# usb_speaker.net
KiCad netlist of a schematic drawn in EAGLE
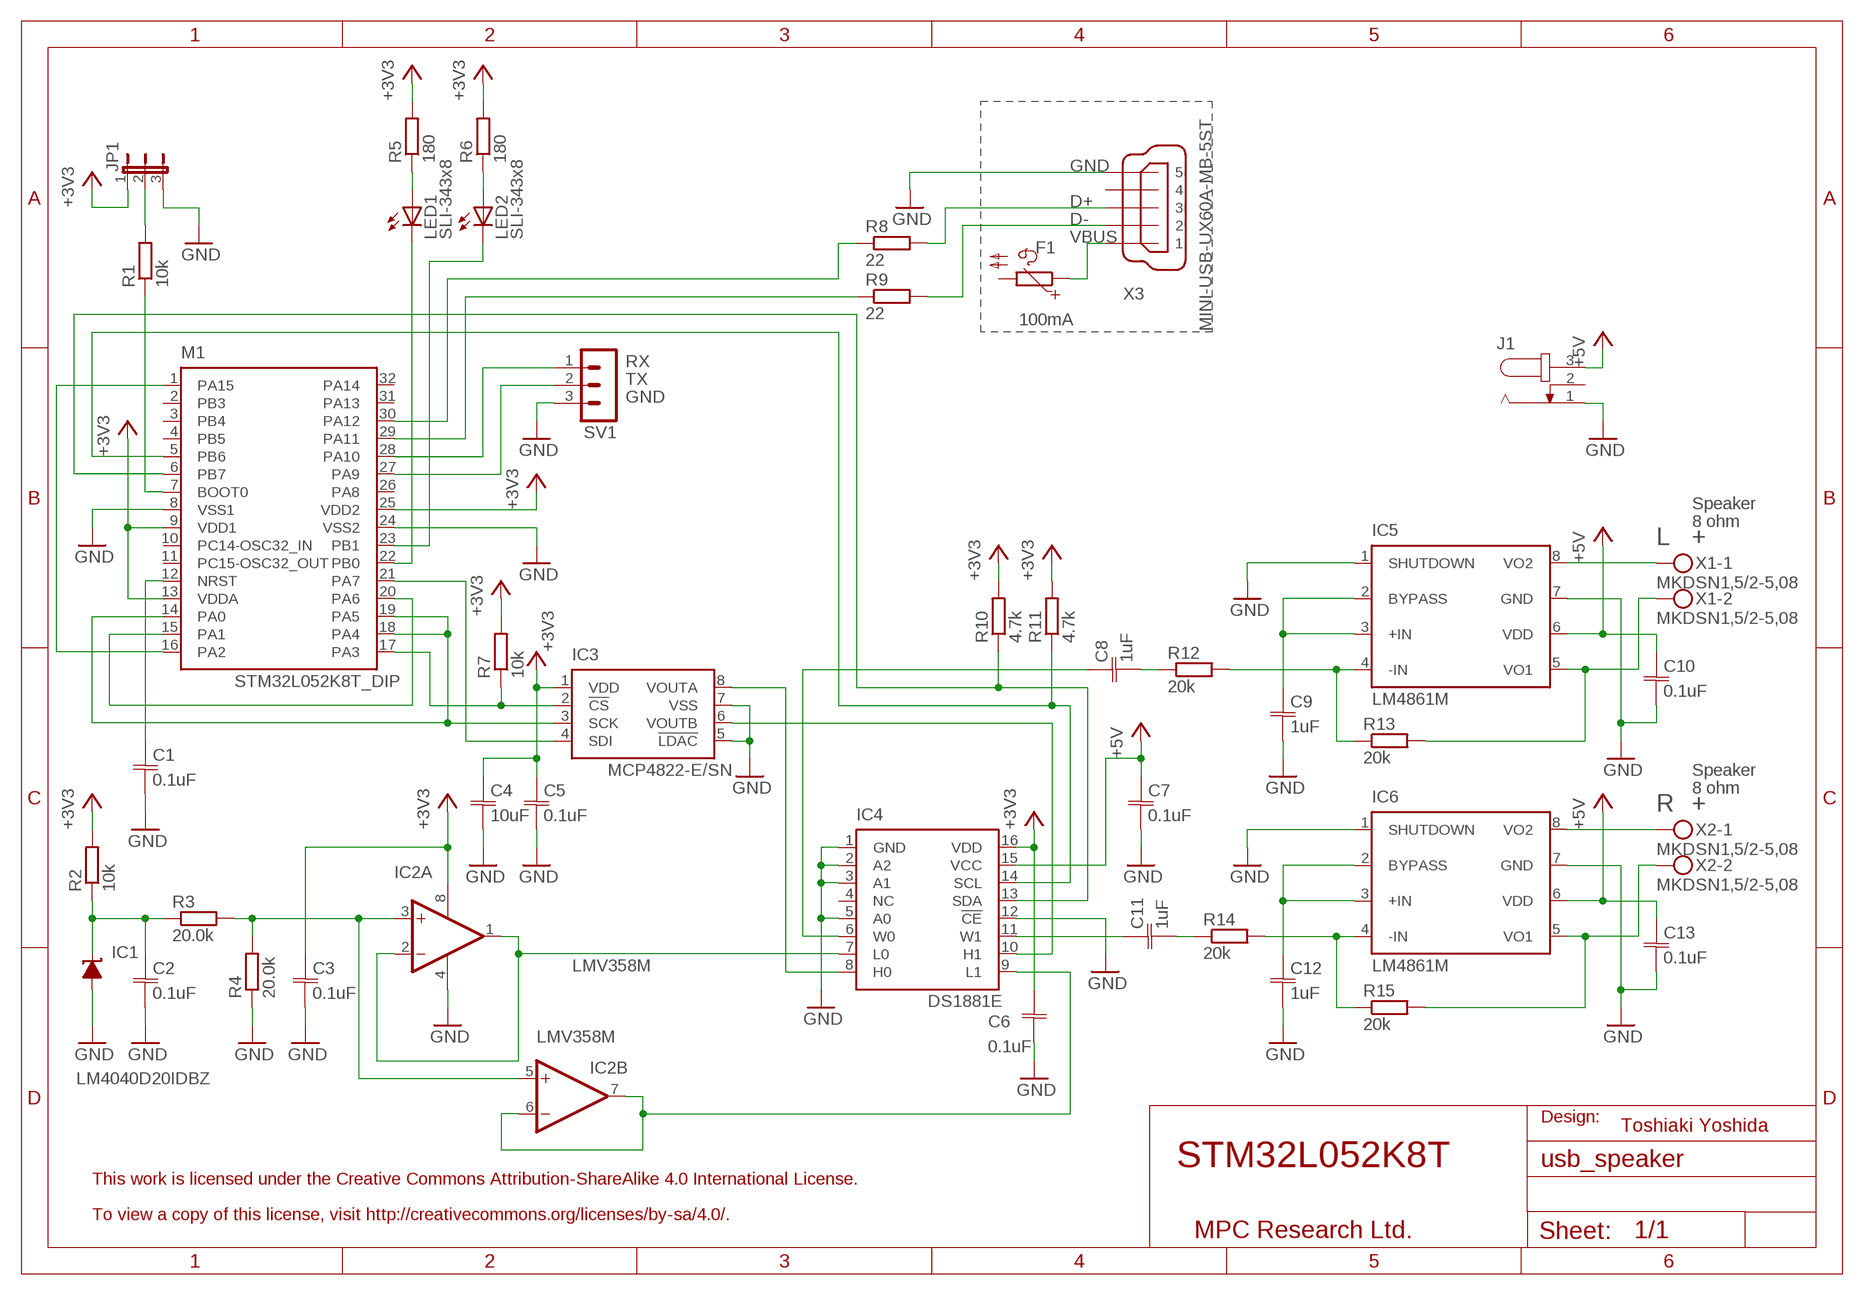
[diagram p0: schematic, sheet 1]

(export (version "E")
  (design (tool "Eeschema 10.0.6"))
  (components
    (comp (ref "C1")
      (value "0.1uF")
      (footprint "eagle-import:C050-024X044")
      (libsource (lib "eagle-import") (part "C-JIS050-024X044"))
    )
    (comp (ref "C2")
      (value "0.1uF")
      (footprint "eagle-import:C050-024X044")
      (libsource (lib "eagle-import") (part "C-JIS050-024X044"))
    )
    (comp (ref "C3")
      (value "0.1uF")
      (footprint "eagle-import:C050-024X044")
      (libsource (lib "eagle-import") (part "C-JIS050-024X044"))
    )
    (comp (ref "C4")
      (value "10uF")
      (footprint "eagle-import:C050-024X044")
      (libsource (lib "eagle-import") (part "C-JIS050-024X044"))
    )
    (comp (ref "C5")
      (value "0.1uF")
      (footprint "eagle-import:C050-024X044")
      (libsource (lib "eagle-import") (part "C-JIS050-024X044"))
    )
    (comp (ref "C6")
      (value "0.1uF")
      (footprint "eagle-import:C050-024X044")
      (libsource (lib "eagle-import") (part "C-JIS050-024X044"))
    )
    (comp (ref "C7")
      (value "0.1uF")
      (footprint "eagle-import:C050-024X044")
      (libsource (lib "eagle-import") (part "C-JIS050-024X044"))
    )
    (comp (ref "C8")
      (value "1uF")
      (footprint "eagle-import:C050-024X044")
      (libsource (lib "eagle-import") (part "C-JIS050-024X044"))
    )
    (comp (ref "C9")
      (value "1uF")
      (footprint "eagle-import:C050-024X044")
      (libsource (lib "eagle-import") (part "C-JIS050-024X044"))
    )
    (comp (ref "C10")
      (value "0.1uF")
      (footprint "eagle-import:C050-024X044")
      (libsource (lib "eagle-import") (part "C-JIS050-024X044"))
    )
    (comp (ref "C11")
      (value "1uF")
      (footprint "eagle-import:C050-024X044")
      (libsource (lib "eagle-import") (part "C-JIS050-024X044"))
    )
    (comp (ref "C12")
      (value "1uF")
      (footprint "eagle-import:C050-024X044")
      (libsource (lib "eagle-import") (part "C-JIS050-024X044"))
    )
    (comp (ref "C13")
      (value "0.1uF")
      (footprint "eagle-import:C050-024X044")
      (libsource (lib "eagle-import") (part "C-JIS050-024X044"))
    )
    (comp (ref "F1")
      (value "100mA")
      (footprint "eagle-import:1206")
      (libsource (lib "eagle-import") (part "PTC1206"))
    )
    (comp (ref "IC1")
      (value "LM4040D20IDBZ")
      (footprint "eagle-import:DBZ_R-PDSO-G3")
      (fields (field (name "MPN") "LM4041A12IDBZR"))
      (libsource (lib "eagle-import") (part "LM4041DBZA12"))
    )
    (comp (ref "IC2")
      (value "LMV358M")
      (footprint "eagle-import:SO08")
      (libsource (lib "eagle-import") (part "LMV358?M"))
    )
    (comp (ref "IC3")
      (value "MCP4822-E/SN")
      (footprint "eagle-import:SO-08")
      (libsource (lib "eagle-import") (part "MCP482-E/SN2"))
    )
    (comp (ref "IC4")
      (value "DS1881E")
      (footprint "eagle-import:TSSP16")
      (libsource (lib "eagle-import") (part "DS1881E"))
    )
    (comp (ref "IC5")
      (value "LM4861M")
      (footprint "eagle-import:SO-08")
      (libsource (lib "eagle-import") (part "LM4861M"))
    )
    (comp (ref "IC6")
      (value "LM4861M")
      (footprint "eagle-import:SO-08")
      (libsource (lib "eagle-import") (part "LM4861M"))
    )
    (comp (ref "J1")
      (value "JACK-PLUG0")
      (footprint "eagle-import:SPC4077")
      (libsource (lib "eagle-import") (part "JACK-PLUG0"))
    )
    (comp (ref "JP1")
      (value "JP2E")
      (footprint "eagle-import:JP2")
      (libsource (lib "eagle-import") (part "JP2E"))
    )
    (comp (ref "LED1")
      (value "SLI-343x8")
      (footprint "eagle-import:LED3MM")
      (libsource (lib "eagle-import") (part "LED3MM"))
    )
    (comp (ref "LED2")
      (value "SLI-343x8")
      (footprint "eagle-import:LED3MM")
      (libsource (lib "eagle-import") (part "LED3MM"))
    )
    (comp (ref "M1")
      (value "STM32L052K8T_DIP")
      (footprint "eagle-import:DIP32")
      (libsource (lib "eagle-import") (part "STM32L052K8T_DIP"))
    )
    (comp (ref "R1")
      (value "10k")
      (footprint "eagle-import:0207_2V")
      (libsource (lib "eagle-import") (part "R-EU_0207/2V"))
    )
    (comp (ref "R2")
      (value "10k")
      (footprint "eagle-import:0207_2V")
      (libsource (lib "eagle-import") (part "R-EU_0207/2V"))
    )
    (comp (ref "R3")
      (value "20.0k")
      (footprint "eagle-import:0207_2V")
      (libsource (lib "eagle-import") (part "R-EU_0207/2V"))
    )
    (comp (ref "R4")
      (value "20.0k")
      (footprint "eagle-import:0207_2V")
      (libsource (lib "eagle-import") (part "R-EU_0207/2V"))
    )
    (comp (ref "R5")
      (value "180")
      (footprint "eagle-import:0207_2V")
      (libsource (lib "eagle-import") (part "R-EU_0207/2V"))
    )
    (comp (ref "R6")
      (value "180")
      (footprint "eagle-import:0207_2V")
      (libsource (lib "eagle-import") (part "R-EU_0207/2V"))
    )
    (comp (ref "R7")
      (value "10k")
      (footprint "eagle-import:0207_2V")
      (libsource (lib "eagle-import") (part "R-EU_0207/2V"))
    )
    (comp (ref "R8")
      (value "22")
      (footprint "eagle-import:0207_10")
      (libsource (lib "eagle-import") (part "R-EU_0207/10"))
    )
    (comp (ref "R9")
      (value "22")
      (footprint "eagle-import:0207_10")
      (libsource (lib "eagle-import") (part "R-EU_0207/10"))
    )
    (comp (ref "R10")
      (value "4.7k")
      (footprint "eagle-import:0207_2V")
      (libsource (lib "eagle-import") (part "R-EU_0207/2V"))
    )
    (comp (ref "R11")
      (value "4.7k")
      (footprint "eagle-import:0207_2V")
      (libsource (lib "eagle-import") (part "R-EU_0207/2V"))
    )
    (comp (ref "R12")
      (value "20k")
      (footprint "eagle-import:0207_2V")
      (libsource (lib "eagle-import") (part "R-EU_0207/2V"))
    )
    (comp (ref "R13")
      (value "20k")
      (footprint "eagle-import:0207_10")
      (libsource (lib "eagle-import") (part "R-EU_0207/10"))
    )
    (comp (ref "R14")
      (value "20k")
      (footprint "eagle-import:0207_2V")
      (libsource (lib "eagle-import") (part "R-EU_0207/2V"))
    )
    (comp (ref "R15")
      (value "20k")
      (footprint "eagle-import:0207_10")
      (libsource (lib "eagle-import") (part "R-EU_0207/10"))
    )
    (comp (ref "SV1")
      (value "MA03-1")
      (footprint "eagle-import:MA03-1")
      (libsource (lib "eagle-import") (part "MA03-1"))
    )
    (comp (ref "X1")
      (value "MKDSN1,5/2-5,08")
      (footprint "eagle-import:MKDSN1,5_2-5,08")
      (libsource (lib "eagle-import") (part "MKDSN1,5/2-5,08"))
    )
    (comp (ref "X2")
      (value "MKDSN1,5/2-5,08")
      (footprint "eagle-import:MKDSN1,5_2-5,08")
      (libsource (lib "eagle-import") (part "MKDSN1,5/2-5,08"))
    )
    (comp (ref "X3")
      (value "MINI-USB-UX60A-MB-5ST")
      (footprint "eagle-import:UX60A-MB-5ST")
      (libsource (lib "eagle-import") (part "MINI-USB-UX60A-MB-5ST"))
    )
  )
  (nets
    (net (code "1") (name "+3V3") (class "Default")
      (node (ref "C3") (pin "1") (pinfunction "1_1") (pintype "passive"))
      (node (ref "C4") (pin "1") (pinfunction "1_1") (pintype "passive"))
      (node (ref "C5") (pin "1") (pinfunction "1_1") (pintype "passive"))
      (node (ref "C6") (pin "1") (pinfunction "1_1") (pintype "passive"))
      (node (ref "IC2") (pin "8") (pinfunction "V+_8") (pintype "power_in"))
      (node (ref "IC3") (pin "1") (pinfunction "VDD_1") (pintype "power_in"))
      (node (ref "IC4") (pin "16") (pinfunction "VDD_16") (pintype "power_in"))
      (node (ref "JP1") (pin "1") (pinfunction "1_1") (pintype "passive"))
      (node (ref "M1") (pin "13") (pinfunction "VDDA_13") (pintype "power_in"))
      (node (ref "M1") (pin "25") (pinfunction "VDD2_25") (pintype "bidirectional"))
      (node (ref "M1") (pin "9") (pinfunction "VDD1_9") (pintype "power_in"))
      (node (ref "R10") (pin "2") (pinfunction "2_2") (pintype "passive"))
      (node (ref "R11") (pin "2") (pinfunction "2_2") (pintype "passive"))
      (node (ref "R2") (pin "2") (pinfunction "2_2") (pintype "passive"))
      (node (ref "R5") (pin "2") (pinfunction "2_2") (pintype "passive"))
      (node (ref "R6") (pin "2") (pinfunction "2_2") (pintype "passive"))
      (node (ref "R7") (pin "2") (pinfunction "2_2") (pintype "passive"))
    )
    (net (code "2") (name "+5V") (class "Default")
      (node (ref "C10") (pin "1") (pinfunction "1_1") (pintype "passive"))
      (node (ref "C13") (pin "1") (pinfunction "1_1") (pintype "passive"))
      (node (ref "C7") (pin "1") (pinfunction "1_1") (pintype "passive"))
      (node (ref "IC4") (pin "15") (pinfunction "VCC_15") (pintype "power_in"))
      (node (ref "IC5") (pin "6") (pinfunction "VDD_6") (pintype "power_in"))
      (node (ref "IC6") (pin "6") (pinfunction "VDD_6") (pintype "power_in"))
      (node (ref "J1") (pin "3") (pinfunction "3_3") (pintype "passive"))
    )
    (net (code "3") (name "GND") (class "Default")
      (node (ref "C1") (pin "2") (pinfunction "2_2") (pintype "passive"))
      (node (ref "C10") (pin "2") (pinfunction "2_2") (pintype "passive"))
      (node (ref "C12") (pin "2") (pinfunction "2_2") (pintype "passive"))
      (node (ref "C13") (pin "2") (pinfunction "2_2") (pintype "passive"))
      (node (ref "C2") (pin "2") (pinfunction "2_2") (pintype "passive"))
      (node (ref "C3") (pin "2") (pinfunction "2_2") (pintype "passive"))
      (node (ref "C4") (pin "2") (pinfunction "2_2") (pintype "passive"))
      (node (ref "C5") (pin "2") (pinfunction "2_2") (pintype "passive"))
      (node (ref "C6") (pin "2") (pinfunction "2_2") (pintype "passive"))
      (node (ref "C7") (pin "2") (pinfunction "2_2") (pintype "passive"))
      (node (ref "C9") (pin "2") (pinfunction "2_2") (pintype "passive"))
      (node (ref "IC1") (pin "2") (pinfunction "A_2") (pintype "passive"))
      (node (ref "IC2") (pin "4") (pinfunction "V-_4") (pintype "power_in"))
      (node (ref "IC3") (pin "5") (pinfunction "~{LDAC}_5") (pintype "input"))
      (node (ref "IC3") (pin "7") (pinfunction "VSS_7") (pintype "power_in"))
      (node (ref "IC4") (pin "1") (pinfunction "GND_1") (pintype "power_in"))
      (node (ref "IC4") (pin "12") (pinfunction "~{CE}_12") (pintype "input"))
      (node (ref "IC4") (pin "2") (pinfunction "A2_2") (pintype "input"))
      (node (ref "IC4") (pin "3") (pinfunction "A1_3") (pintype "input"))
      (node (ref "IC4") (pin "5") (pinfunction "A0_5") (pintype "input"))
      (node (ref "IC5") (pin "1") (pinfunction "SHUTDOWN_1") (pintype "input"))
      (node (ref "IC5") (pin "7") (pinfunction "GND_7") (pintype "power_in"))
      (node (ref "IC6") (pin "1") (pinfunction "SHUTDOWN_1") (pintype "input"))
      (node (ref "IC6") (pin "7") (pinfunction "GND_7") (pintype "power_in"))
      (node (ref "J1") (pin "1") (pinfunction "1_1") (pintype "passive"))
      (node (ref "JP1") (pin "3") (pinfunction "3_3") (pintype "passive"))
      (node (ref "M1") (pin "24") (pinfunction "VSS2_24") (pintype "power_in"))
      (node (ref "M1") (pin "8") (pinfunction "VSS1_8") (pintype "power_in"))
      (node (ref "R4") (pin "1") (pinfunction "1_1") (pintype "passive"))
      (node (ref "SV1") (pin "3") (pinfunction "3_3") (pintype "passive"))
      (node (ref "X3") (pin "5") (pinfunction "5_5") (pintype "input"))
    )
    (net (code "4") (name "Net-(C8-Pad2)") (class "Default")
      (node (ref "C8") (pin "2") (pinfunction "2_2") (pintype "passive"))
      (node (ref "R12") (pin "1") (pinfunction "1_1") (pintype "passive"))
    )
    (net (code "5") (name "Net-(C11-Pad2)") (class "Default")
      (node (ref "C11") (pin "2") (pinfunction "2_2") (pintype "passive"))
      (node (ref "R14") (pin "1") (pinfunction "1_1") (pintype "passive"))
    )
    (net (code "6") (name "Net-(F1-Pad1)") (class "Default")
      (node (ref "F1") (pin "1") (pinfunction "1_1") (pintype "passive"))
      (node (ref "X3") (pin "1") (pinfunction "1_1") (pintype "input"))
    )
    (net (code "7") (name "Net-(IC1-C)") (class "Default")
      (node (ref "C2") (pin "1") (pinfunction "1_1") (pintype "passive"))
      (node (ref "IC1") (pin "1") (pinfunction "C_1") (pintype "passive"))
      (node (ref "R2") (pin "1") (pinfunction "1_1") (pintype "passive"))
      (node (ref "R3") (pin "1") (pinfunction "1_1") (pintype "passive"))
    )
    (net (code "8") (name "Net-(IC2A-+IN)") (class "Default")
      (node (ref "IC2") (pin "3") (pinfunction "+IN_3") (pintype "input"))
      (node (ref "IC2") (pin "5") (pinfunction "+IN_5") (pintype "input"))
      (node (ref "R3") (pin "2") (pinfunction "2_2") (pintype "passive"))
      (node (ref "R4") (pin "2") (pinfunction "2_2") (pintype "passive"))
    )
    (net (code "9") (name "Net-(IC2A--IN)") (class "Default")
      (node (ref "IC2") (pin "1") (pinfunction "OUT_1") (pintype "output"))
      (node (ref "IC2") (pin "2") (pinfunction "-IN_2") (pintype "input"))
      (node (ref "IC4") (pin "7") (pinfunction "L0_7") (pintype "passive"))
    )
    (net (code "10") (name "Net-(IC2B--IN)") (class "Default")
      (node (ref "IC2") (pin "6") (pinfunction "-IN_6") (pintype "input"))
      (node (ref "IC2") (pin "7") (pinfunction "OUT_7") (pintype "output"))
      (node (ref "IC4") (pin "9") (pinfunction "L1_9") (pintype "passive"))
    )
    (net (code "11") (name "Net-(IC3-SCK)") (class "Default")
      (node (ref "IC3") (pin "3") (pinfunction "SCK_3") (pintype "input"))
      (node (ref "M1") (pin "14") (pinfunction "PA0_14") (pintype "bidirectional"))
      (node (ref "M1") (pin "18") (pinfunction "PA4_18") (pintype "bidirectional"))
      (node (ref "M1") (pin "19") (pinfunction "PA5_19") (pintype "bidirectional"))
    )
    (net (code "12") (name "Net-(IC3-SDI)") (class "Default")
      (node (ref "IC3") (pin "4") (pinfunction "SDI_4") (pintype "input"))
      (node (ref "M1") (pin "21") (pinfunction "PA7_21") (pintype "bidirectional"))
    )
    (net (code "13") (name "Net-(IC3-VOUTA)") (class "Default")
      (node (ref "IC3") (pin "8") (pinfunction "VOUTA_8") (pintype "output"))
      (node (ref "IC4") (pin "8") (pinfunction "H0_8") (pintype "passive"))
    )
    (net (code "14") (name "Net-(IC3-VOUTB)") (class "Default")
      (node (ref "IC3") (pin "6") (pinfunction "VOUTB_6") (pintype "output"))
      (node (ref "IC4") (pin "10") (pinfunction "H1_10") (pintype "passive"))
    )
    (net (code "15") (name "Net-(IC3-~{CS})") (class "Default")
      (node (ref "IC3") (pin "2") (pinfunction "~{CS}_2") (pintype "input"))
      (node (ref "M1") (pin "17") (pinfunction "PA3_17") (pintype "bidirectional"))
      (node (ref "R7") (pin "1") (pinfunction "1_1") (pintype "passive"))
    )
    (net (code "16") (name "Net-(IC4-SCL)") (class "Default")
      (node (ref "IC4") (pin "14") (pinfunction "SCL_14") (pintype "input"))
      (node (ref "M1") (pin "5") (pinfunction "PB6_5") (pintype "bidirectional"))
      (node (ref "R11") (pin "1") (pinfunction "1_1") (pintype "passive"))
    )
    (net (code "17") (name "Net-(IC4-SDA)") (class "Default")
      (node (ref "IC4") (pin "13") (pinfunction "SDA_13") (pintype "bidirectional"))
      (node (ref "M1") (pin "6") (pinfunction "PB7_6") (pintype "bidirectional"))
      (node (ref "R10") (pin "1") (pinfunction "1_1") (pintype "passive"))
    )
    (net (code "18") (name "Net-(IC4-W0)") (class "Default")
      (node (ref "C8") (pin "1") (pinfunction "1_1") (pintype "passive"))
      (node (ref "IC4") (pin "6") (pinfunction "W0_6") (pintype "passive"))
    )
    (net (code "19") (name "Net-(IC4-W1)") (class "Default")
      (node (ref "C11") (pin "1") (pinfunction "1_1") (pintype "passive"))
      (node (ref "IC4") (pin "11") (pinfunction "W1_11") (pintype "passive"))
    )
    (net (code "20") (name "Net-(IC5-+IN)") (class "Default")
      (node (ref "C9") (pin "1") (pinfunction "1_1") (pintype "passive"))
      (node (ref "IC5") (pin "2") (pinfunction "BYPASS_2") (pintype "passive"))
      (node (ref "IC5") (pin "3") (pinfunction "+IN_3") (pintype "input"))
    )
    (net (code "21") (name "Net-(IC5--IN)") (class "Default")
      (node (ref "IC5") (pin "4") (pinfunction "-IN_4") (pintype "input"))
      (node (ref "R12") (pin "2") (pinfunction "2_2") (pintype "passive"))
      (node (ref "R13") (pin "1") (pinfunction "1_1") (pintype "passive"))
    )
    (net (code "22") (name "Net-(IC5-VO1)") (class "Default")
      (node (ref "IC5") (pin "5") (pinfunction "VO1_5") (pintype "output"))
      (node (ref "R13") (pin "2") (pinfunction "2_2") (pintype "passive"))
      (node (ref "X1") (pin "2") (pinfunction "KL_2") (pintype "passive"))
    )
    (net (code "23") (name "Net-(IC5-VO2)") (class "Default")
      (node (ref "IC5") (pin "8") (pinfunction "VO2_8") (pintype "output"))
      (node (ref "X1") (pin "1") (pinfunction "KL_1") (pintype "passive"))
    )
    (net (code "24") (name "Net-(IC6-+IN)") (class "Default")
      (node (ref "C12") (pin "1") (pinfunction "1_1") (pintype "passive"))
      (node (ref "IC6") (pin "2") (pinfunction "BYPASS_2") (pintype "passive"))
      (node (ref "IC6") (pin "3") (pinfunction "+IN_3") (pintype "input"))
    )
    (net (code "25") (name "Net-(IC6--IN)") (class "Default")
      (node (ref "IC6") (pin "4") (pinfunction "-IN_4") (pintype "input"))
      (node (ref "R14") (pin "2") (pinfunction "2_2") (pintype "passive"))
      (node (ref "R15") (pin "1") (pinfunction "1_1") (pintype "passive"))
    )
    (net (code "26") (name "Net-(IC6-VO1)") (class "Default")
      (node (ref "IC6") (pin "5") (pinfunction "VO1_5") (pintype "output"))
      (node (ref "R15") (pin "2") (pinfunction "2_2") (pintype "passive"))
      (node (ref "X2") (pin "2") (pinfunction "KL_2") (pintype "passive"))
    )
    (net (code "27") (name "Net-(IC6-VO2)") (class "Default")
      (node (ref "IC6") (pin "8") (pinfunction "VO2_8") (pintype "output"))
      (node (ref "X2") (pin "1") (pinfunction "KL_1") (pintype "passive"))
    )
    (net (code "28") (name "Net-(JP1-Pad2)") (class "Default")
      (node (ref "JP1") (pin "2") (pinfunction "2_2") (pintype "passive"))
      (node (ref "R1") (pin "2") (pinfunction "2_2") (pintype "passive"))
    )
    (net (code "29") (name "Net-(LED1-C)") (class "Default")
      (node (ref "LED1") (pin "K") (pinfunction "C_K") (pintype "passive"))
      (node (ref "M1") (pin "22") (pinfunction "PB0_22") (pintype "bidirectional"))
    )
    (net (code "30") (name "Net-(LED1-PadA)") (class "Default")
      (node (ref "LED1") (pin "A") (pinfunction "A_A") (pintype "passive"))
      (node (ref "R5") (pin "1") (pinfunction "1_1") (pintype "passive"))
    )
    (net (code "31") (name "Net-(LED2-C)") (class "Default")
      (node (ref "LED2") (pin "K") (pinfunction "C_K") (pintype "passive"))
      (node (ref "M1") (pin "23") (pinfunction "PB1_23") (pintype "bidirectional"))
    )
    (net (code "32") (name "Net-(LED2-PadA)") (class "Default")
      (node (ref "LED2") (pin "A") (pinfunction "A_A") (pintype "passive"))
      (node (ref "R6") (pin "1") (pinfunction "1_1") (pintype "passive"))
    )
    (net (code "33") (name "Net-(M1-BOOT0)") (class "Default")
      (node (ref "M1") (pin "7") (pinfunction "BOOT0_7") (pintype "bidirectional"))
      (node (ref "R1") (pin "1") (pinfunction "1_1") (pintype "passive"))
    )
    (net (code "34") (name "Net-(M1-NRST)") (class "Default")
      (node (ref "C1") (pin "1") (pinfunction "1_1") (pintype "passive"))
      (node (ref "M1") (pin "12") (pinfunction "NRST_12") (pintype "bidirectional"))
    )
    (net (code "35") (name "Net-(M1-PA1)") (class "Default")
      (node (ref "M1") (pin "15") (pinfunction "PA1_15") (pintype "bidirectional"))
      (node (ref "M1") (pin "20") (pinfunction "PA6_20") (pintype "bidirectional"))
    )
    (net (code "36") (name "Net-(M1-PA9)") (class "Default")
      (node (ref "M1") (pin "27") (pinfunction "PA9_27") (pintype "bidirectional"))
      (node (ref "SV1") (pin "2") (pinfunction "2_2") (pintype "passive"))
    )
    (net (code "37") (name "Net-(M1-PA10)") (class "Default")
      (node (ref "M1") (pin "28") (pinfunction "PA10_28") (pintype "bidirectional"))
      (node (ref "SV1") (pin "1") (pinfunction "1_1") (pintype "passive"))
    )
    (net (code "38") (name "Net-(M1-PA11)") (class "Default")
      (node (ref "M1") (pin "29") (pinfunction "PA11_29") (pintype "bidirectional"))
      (node (ref "R9") (pin "1") (pinfunction "1_1") (pintype "passive"))
    )
    (net (code "39") (name "Net-(M1-PA12)") (class "Default")
      (node (ref "M1") (pin "30") (pinfunction "PA12_30") (pintype "bidirectional"))
      (node (ref "R8") (pin "1") (pinfunction "1_1") (pintype "passive"))
    )
    (net (code "40") (name "Net-(M1-PA15)") (class "Default")
      (node (ref "M1") (pin "1") (pinfunction "PA15_1") (pintype "bidirectional"))
      (node (ref "M1") (pin "16") (pinfunction "PA2_16") (pintype "bidirectional"))
    )
    (net (code "41") (name "Net-(R8-Pad2)") (class "Default")
      (node (ref "R8") (pin "2") (pinfunction "2_2") (pintype "passive"))
      (node (ref "X3") (pin "3") (pinfunction "3_3") (pintype "input"))
    )
    (net (code "42") (name "Net-(R9-Pad2)") (class "Default")
      (node (ref "R9") (pin "2") (pinfunction "2_2") (pintype "passive"))
      (node (ref "X3") (pin "2") (pinfunction "2_2") (pintype "input"))
    )
    (net (code "43") (name "unconnected-(F1-Pad2)") (class "Default")
      (node (ref "F1") (pin "2") (pinfunction "2_2") (pintype "passive"))
    )
    (net (code "44") (name "unconnected-(IC4-NC-Pad4)") (class "Default")
      (node (ref "IC4") (pin "4") (pinfunction "NC_4") (pintype "no_connect"))
    )
    (net (code "45") (name "unconnected-(J1-Pad2)") (class "Default")
      (node (ref "J1") (pin "2") (pinfunction "2_2") (pintype "passive"))
    )
    (net (code "46") (name "unconnected-(M1-PA8-Pad26)") (class "Default")
      (node (ref "M1") (pin "26") (pinfunction "PA8_26") (pintype "bidirectional"))
    )
    (net (code "47") (name "unconnected-(M1-PA13-Pad31)") (class "Default")
      (node (ref "M1") (pin "31") (pinfunction "PA13_31") (pintype "bidirectional"))
    )
    (net (code "48") (name "unconnected-(M1-PA14-Pad32)") (class "Default")
      (node (ref "M1") (pin "32") (pinfunction "PA14_32") (pintype "bidirectional"))
    )
    (net (code "49") (name "unconnected-(M1-PB3-Pad2)") (class "Default")
      (node (ref "M1") (pin "2") (pinfunction "PB3_2") (pintype "bidirectional"))
    )
    (net (code "50") (name "unconnected-(M1-PB4-Pad3)") (class "Default")
      (node (ref "M1") (pin "3") (pinfunction "PB4_3") (pintype "bidirectional"))
    )
    (net (code "51") (name "unconnected-(M1-PB5-Pad4)") (class "Default")
      (node (ref "M1") (pin "4") (pinfunction "PB5_4") (pintype "bidirectional"))
    )
    (net (code "52") (name "unconnected-(M1-PC14-OSC32_IN-Pad10)") (class "Default")
      (node (ref "M1") (pin "10") (pinfunction "PC14-OSC32_IN_10") (pintype "bidirectional"))
    )
    (net (code "53") (name "unconnected-(M1-PC15-OSC32_OUT-Pad11)") (class "Default")
      (node (ref "M1") (pin "11") (pinfunction "PC15-OSC32_OUT_11") (pintype "bidirectional"))
    )
    (net (code "54") (name "unconnected-(X3-Pad4)") (class "Default")
      (node (ref "X3") (pin "4") (pinfunction "4_4") (pintype "input"))
    )
  )
)
